# mcu.net
KiCad netlist of a schematic drawn in Altium Designer
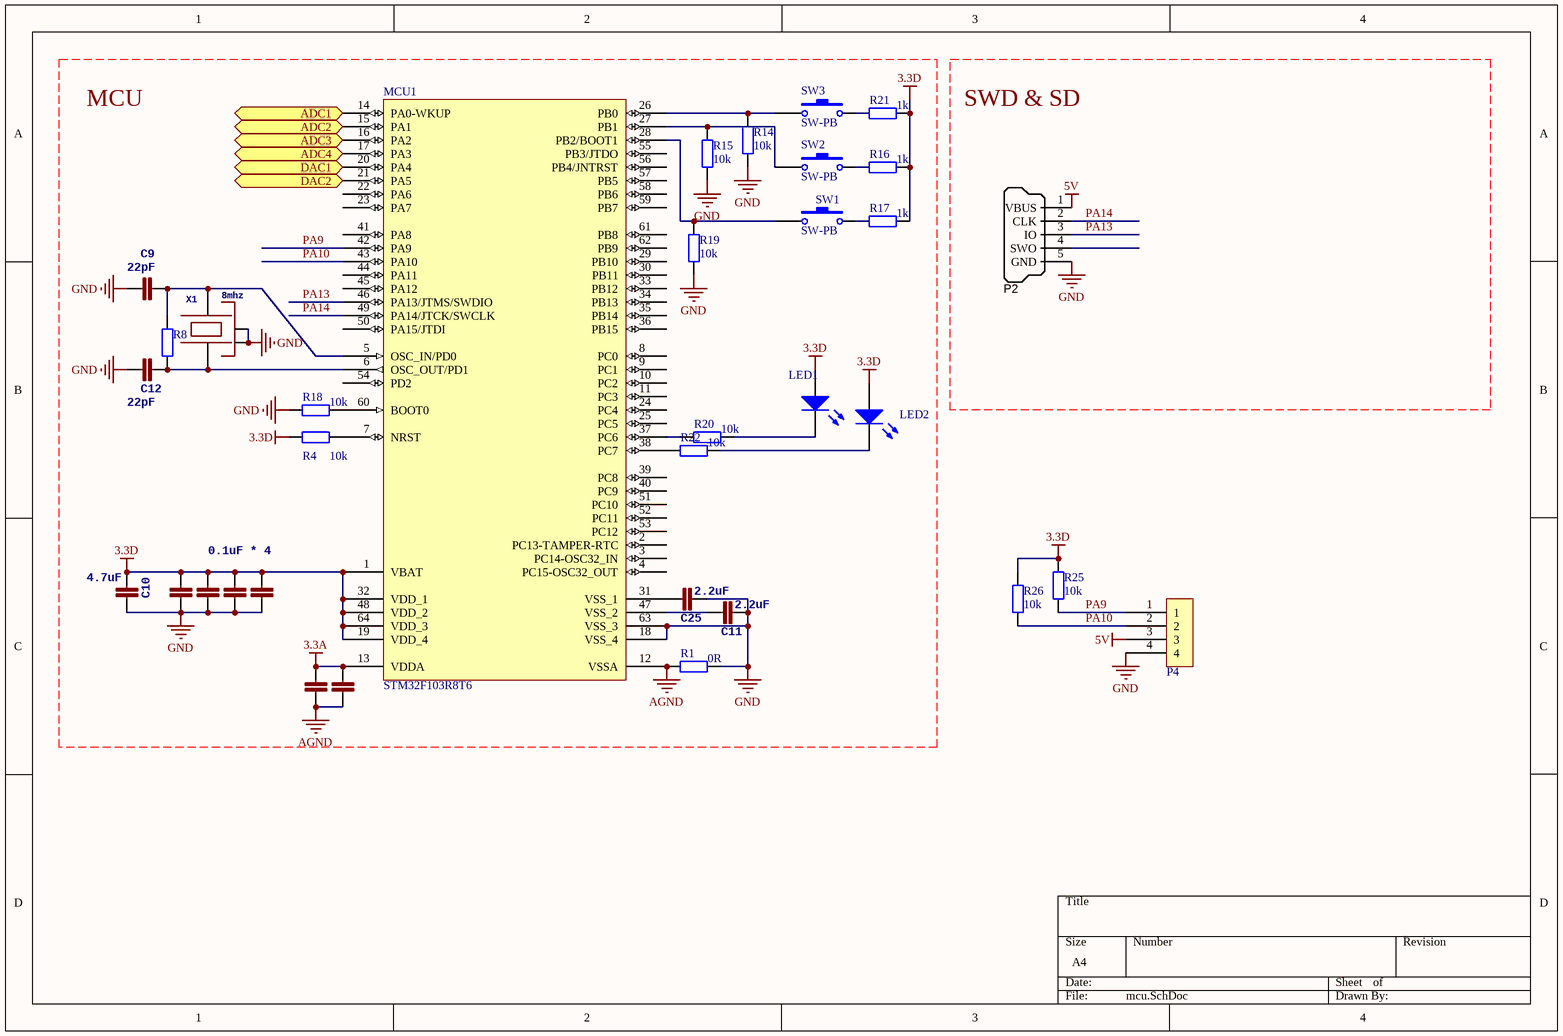
[diagram p0: mcu.SchDoc]

(export (version "E")
  (design (tool "Eeschema 10.0.6"))
  (components
    (comp (ref "C3")
      (value "1n")
      (footprint "0402")
      (description "<b>Capacitor</b>\nStandard 0603 ceramic capacitor, and 0.1\" leaded capacitor.")
      (fields (field (name "PARTNO") "CC0402ZRY5V7BB104"))
      (libsource (lib "") (part "CAP0402-CAP_3"))
    )
    (comp (ref "C4")
      (value "0.1uF * 4")
      (footprint "0402")
      (description "<b>Capacitor</b>\nStandard 0603 ceramic capacitor, and 0.1\" leaded capacitor.")
      (fields (field (name "PARTNO") "CC0402ZRY5V7BB104"))
      (libsource (lib "*") (part "CAP0402-CAP"))
    )
    (comp (ref "C5")
      (value "1n")
      (footprint "0402")
      (description "<b>Capacitor</b>\nStandard 0603 ceramic capacitor, and 0.1\" leaded capacitor.")
      (fields (field (name "PARTNO") "CC0402ZRY5V7BB104"))
      (libsource (lib "") (part "CAP0402-CAP_1"))
    )
    (comp (ref "C6")
      (value "1n")
      (footprint "0402")
      (description "<b>Capacitor</b>\nStandard 0603 ceramic capacitor, and 0.1\" leaded capacitor.")
      (fields (field (name "PARTNO") "CC0402ZRY5V7BB104"))
      (libsource (lib "") (part "CAP0402-CAP_1"))
    )
    (comp (ref "C7")
      (value "1n")
      (footprint "0402")
      (description "<b>Capacitor</b>\nStandard 0603 ceramic capacitor, and 0.1\" leaded capacitor.")
      (fields (field (name "PARTNO") "CC0402ZRY5V7BB104"))
      (libsource (lib "") (part "CAP0402-CAP_1"))
    )
    (comp (ref "C8")
      (value "1n")
      (footprint "0402")
      (description "<b>Capacitor</b>\nStandard 0603 ceramic capacitor, and 0.1\" leaded capacitor.")
      (fields (field (name "PARTNO") "CC0402ZRY5V7BB104"))
      (libsource (lib "") (part "CAP0402-CAP_3"))
    )
    (comp (ref "C9")
      (value "22pF")
      (footprint "0402")
      (description "<b>Capacitor</b>\nStandard 0603 ceramic capacitor, and 0.1\" leaded capacitor.")
      (fields (field (name "PARTNO") "CC0402ZRY5V7BB104"))
      (libsource (lib "pixhawk2") (part "CAP0402-CAP"))
    )
    (comp (ref "C10")
      (value "4.7uF")
      (footprint "0603")
      (description "<b>Capacitor</b>\nStandard 0603 ceramic capacitor, and 0.1\" leaded capacitor.")
      (fields (field (name "PARTNO") "CC0402ZRY5V7BB104"))
      (libsource (lib "") (part "CAP0402-CAP_1"))
    )
    (comp (ref "C11")
      (value "2.2uF")
      (footprint "0603")
      (description "<b>Capacitor</b>\nStandard 0603 ceramic capacitor, and 0.1\" leaded capacitor.")
      (fields (field (name "PARTNO") "CC0402ZRY5V7BB104"))
      (libsource (lib "") (part "CAP0402-CAP_2"))
    )
    (comp (ref "C12")
      (value "22pF")
      (footprint "0402")
      (description "<b>Capacitor</b>\nStandard 0603 ceramic capacitor, and 0.1\" leaded capacitor.")
      (fields (field (name "PARTNO") "CC0402ZRY5V7BB104"))
      (libsource (lib "") (part "CAP0402-CAP_1"))
    )
    (comp (ref "C25")
      (value "2.2uF")
      (footprint "0603")
      (description "<b>Capacitor</b>\nStandard 0603 ceramic capacitor, and 0.1\" leaded capacitor.")
      (fields (field (name "PARTNO") "CC0402ZRY5V7BB104"))
      (libsource (lib "") (part "CAP0402-CAP_2"))
    )
    (comp (ref "LED1")
      (value "LED0")
      (footprint "0603")
      (description "Typical INFRARED GaAs LED")
      (fields (field (name "PUBLISHER") "Altium Limited"))
      (libsource (lib "Miscellaneous Devices") (part "LED0"))
    )
    (comp (ref "LED2")
      (value "LED0")
      (footprint "0603")
      (description "Typical INFRARED GaAs LED")
      (fields (field (name "PUBLISHER") "Altium Limited"))
      (libsource (lib "Miscellaneous Devices") (part "LED0"))
    )
    (comp (ref "MCU1")
      (value "STM32F103R8T6")
      (footprint "LQFP64_N")
      (description "STM32 ARM-based 32-bit MCU with 64 Kbytes Flash, 64-pin LQFP, Industrial Temperature")
      (fields (field (name "PUBLISHER") "*"))
      (libsource (lib "ST Microcontroller 32-Bit STM32 SCH") (part "STM32F103R8T6"))
    )
    (comp (ref "P2")
      (value "SWD_MicroUSB")
      (footprint "MICRO-YZX")
      (description "Connector SMD USB Micro Type B middle mount")
      (libsource (lib "sch") (part "SWD_MicroUSB"))
    )
    (comp (ref "P4") (value "UART/I2C") (footprint "4pSocket") (libsource (lib "sch") (part "4PSocket")))
    (comp (ref "R1")
      (value "0R")
      (footprint "0402")
      (description "Resistor")
      (fields (field (name "PUBLISHER") "Altium Limited"))
      (libsource (lib "") (part "Res2_1"))
    )
    (comp (ref "R4")
      (value "10k")
      (footprint "0402")
      (description "Resistor")
      (fields (field (name "PUBLISHER") "Altium Limited"))
      (libsource (lib "") (part "Res2_2"))
    )
    (comp (ref "R8")
      (value "~")
      (footprint "0402")
      (description "Resistor")
      (fields (field (name "PUBLISHER") "Altium Limited"))
      (libsource (lib "Miscellaneous Devices") (part "Res2"))
    )
    (comp (ref "R14")
      (value "10k")
      (footprint "0402")
      (description "Resistor")
      (fields (field (name "PUBLISHER") "Altium Limited"))
      (libsource (lib "Miscellaneous Devices") (part "Res2"))
    )
    (comp (ref "R15")
      (value "10k")
      (footprint "0402")
      (description "Resistor")
      (fields (field (name "PUBLISHER") "Altium Limited"))
      (libsource (lib "Miscellaneous Devices") (part "Res2"))
    )
    (comp (ref "R16")
      (value "1k")
      (footprint "0402")
      (description "Resistor")
      (fields (field (name "PUBLISHER") "Altium Limited"))
      (libsource (lib "") (part "Res2_1"))
    )
    (comp (ref "R17")
      (value "1k")
      (footprint "0402")
      (description "Resistor")
      (fields (field (name "PUBLISHER") "Altium Limited"))
      (libsource (lib "") (part "Res2_1"))
    )
    (comp (ref "R18")
      (value "10k")
      (footprint "0402")
      (description "Resistor")
      (fields (field (name "PUBLISHER") "Altium Limited"))
      (libsource (lib "") (part "Res2_1"))
    )
    (comp (ref "R19")
      (value "10k")
      (footprint "0402")
      (description "Resistor")
      (fields (field (name "PUBLISHER") "Altium Limited"))
      (libsource (lib "Miscellaneous Devices") (part "Res2"))
    )
    (comp (ref "R20")
      (value "10k")
      (footprint "0402")
      (description "Resistor")
      (fields (field (name "PUBLISHER") "Altium Limited"))
      (libsource (lib "") (part "Res2_1"))
    )
    (comp (ref "R21")
      (value "1k")
      (footprint "0402")
      (description "Resistor")
      (fields (field (name "PUBLISHER") "Altium Limited"))
      (libsource (lib "") (part "Res2_1"))
    )
    (comp (ref "R22")
      (value "10k")
      (footprint "0402")
      (description "Resistor")
      (fields (field (name "PUBLISHER") "Altium Limited"))
      (libsource (lib "") (part "Res2_1"))
    )
    (comp (ref "R25")
      (value "10k")
      (footprint "0402")
      (description "Resistor")
      (fields (field (name "PUBLISHER") "Altium Limited"))
      (libsource (lib "Miscellaneous Devices") (part "Res2"))
    )
    (comp (ref "R26")
      (value "10k")
      (footprint "0402")
      (description "Resistor")
      (fields (field (name "PUBLISHER") "Altium Limited"))
      (libsource (lib "Miscellaneous Devices") (part "Res2"))
    )
    (comp (ref "SW1")
      (value "SW-PB")
      (footprint "SW3x4")
      (description "Switch")
      (fields (field (name "PUBLISHER") "Altium Limited"))
      (libsource (lib "Miscellaneous Devices") (part "SW-PB"))
    )
    (comp (ref "SW2")
      (value "SW-PB")
      (footprint "SW3x4")
      (description "Switch")
      (fields (field (name "PUBLISHER") "Altium Limited"))
      (libsource (lib "Miscellaneous Devices") (part "SW-PB"))
    )
    (comp (ref "SW3")
      (value "SW-PB")
      (footprint "SW3x4")
      (description "Switch")
      (fields (field (name "PUBLISHER") "Altium Limited"))
      (libsource (lib "Miscellaneous Devices") (part "SW-PB"))
    )
    (comp (ref "X1")
      (value "8mhz")
      (footprint "OSCILLATOR-3.2X2.5")
      (description "Crystal Oscillator in 3.2x2.5 SMD")
      (libsource (lib "sch") (part "OSCILLATOR-3.2X2.5"))
    )
  )
  (nets
    (net (code "1") (name "/ADC1") (class "Default")
      (node (ref "MCU1") (pin "14") (pinfunction "PA0-WKUP_14") (pintype "bidirectional"))
    )
    (net (code "2") (name "/ADC2") (class "Default")
      (node (ref "MCU1") (pin "15") (pinfunction "PA1_15") (pintype "bidirectional"))
    )
    (net (code "3") (name "/ADC3") (class "Default")
      (node (ref "MCU1") (pin "16") (pinfunction "PA2_16") (pintype "bidirectional"))
    )
    (net (code "4") (name "/ADC4") (class "Default")
      (node (ref "MCU1") (pin "17") (pinfunction "PA3_17") (pintype "bidirectional"))
    )
    (net (code "5") (name "/DAC1") (class "Default")
      (node (ref "MCU1") (pin "20") (pinfunction "PA4_20") (pintype "bidirectional"))
    )
    (net (code "6") (name "/DAC2") (class "Default")
      (node (ref "MCU1") (pin "21") (pinfunction "PA5_21") (pintype "bidirectional"))
    )
    (net (code "7") (name "/PA9") (class "Default")
      (node (ref "MCU1") (pin "42") (pinfunction "PA9_42") (pintype "bidirectional"))
      (node (ref "P4") (pin "1") (pinfunction "1_1") (pintype "passive"))
      (node (ref "R25") (pin "1") (pinfunction "1_1") (pintype "passive"))
    )
    (net (code "8") (name "/PA10") (class "Default")
      (node (ref "MCU1") (pin "43") (pinfunction "PA10_43") (pintype "bidirectional"))
      (node (ref "P4") (pin "2") (pinfunction "2_2") (pintype "passive"))
      (node (ref "R26") (pin "1") (pinfunction "1_1") (pintype "passive"))
    )
    (net (code "9") (name "/PA13") (class "Default")
      (node (ref "MCU1") (pin "46") (pinfunction "PA13/JTMS/SWDIO_46") (pintype "bidirectional"))
      (node (ref "P2") (pin "3") (pinfunction "IO_3") (pintype "passive"))
    )
    (net (code "10") (name "/PA14") (class "Default")
      (node (ref "MCU1") (pin "49") (pinfunction "PA14/JTCK/SWCLK_49") (pintype "bidirectional"))
      (node (ref "P2") (pin "2") (pinfunction "CLK_2") (pintype "passive"))
    )
    (net (code "11") (name "3.3A") (class "Default")
      (node (ref "C3") (pin "1") (pinfunction "1_1") (pintype "passive"))
      (node (ref "C8") (pin "1") (pinfunction "1_1") (pintype "passive"))
      (node (ref "MCU1") (pin "13") (pinfunction "VDDA_13") (pintype "power_in"))
    )
    (net (code "12") (name "3.3D") (class "Default")
      (node (ref "C10") (pin "2") (pinfunction "2_2") (pintype "passive"))
      (node (ref "C4") (pin "2") (pinfunction "2_2") (pintype "passive"))
      (node (ref "C5") (pin "2") (pinfunction "2_2") (pintype "passive"))
      (node (ref "C6") (pin "2") (pinfunction "2_2") (pintype "passive"))
      (node (ref "C7") (pin "2") (pinfunction "2_2") (pintype "passive"))
      (node (ref "LED1") (pin "1") (pinfunction "A_1") (pintype "passive"))
      (node (ref "LED2") (pin "1") (pinfunction "A_1") (pintype "passive"))
      (node (ref "MCU1") (pin "1") (pinfunction "VBAT_1") (pintype "power_in"))
      (node (ref "MCU1") (pin "19") (pinfunction "VDD_4_19") (pintype "power_in"))
      (node (ref "MCU1") (pin "32") (pinfunction "VDD_1_32") (pintype "power_in"))
      (node (ref "MCU1") (pin "48") (pinfunction "VDD_2_48") (pintype "power_in"))
      (node (ref "MCU1") (pin "64") (pinfunction "VDD_3_64") (pintype "power_in"))
      (node (ref "R16") (pin "2") (pinfunction "2_2") (pintype "passive"))
      (node (ref "R17") (pin "2") (pinfunction "2_2") (pintype "passive"))
      (node (ref "R21") (pin "2") (pinfunction "2_2") (pintype "passive"))
      (node (ref "R25") (pin "2") (pinfunction "2_2") (pintype "passive"))
      (node (ref "R26") (pin "2") (pinfunction "2_2") (pintype "passive"))
      (node (ref "R4") (pin "2") (pinfunction "2_2") (pintype "passive"))
    )
    (net (code "13") (name "5V") (class "Default")
      (node (ref "P2") (pin "1") (pinfunction "VBUS_1") (pintype "passive"))
      (node (ref "P4") (pin "3") (pinfunction "3_3") (pintype "passive"))
    )
    (net (code "14") (name "AGND") (class "Default")
      (node (ref "C3") (pin "2") (pinfunction "2_2") (pintype "passive"))
      (node (ref "C8") (pin "2") (pinfunction "2_2") (pintype "passive"))
      (node (ref "MCU1") (pin "12") (pinfunction "VSSA_12") (pintype "power_in"))
      (node (ref "R1") (pin "1") (pinfunction "1_1") (pintype "passive"))
    )
    (net (code "15") (name "GND") (class "Default")
      (node (ref "C10") (pin "1") (pinfunction "1_1") (pintype "passive"))
      (node (ref "C11") (pin "2") (pinfunction "2_2") (pintype "passive"))
      (node (ref "C12") (pin "2") (pinfunction "2_2") (pintype "passive"))
      (node (ref "C25") (pin "2") (pinfunction "2_2") (pintype "passive"))
      (node (ref "C4") (pin "1") (pinfunction "1_1") (pintype "passive"))
      (node (ref "C5") (pin "1") (pinfunction "1_1") (pintype "passive"))
      (node (ref "C6") (pin "1") (pinfunction "1_1") (pintype "passive"))
      (node (ref "C7") (pin "1") (pinfunction "1_1") (pintype "passive"))
      (node (ref "C9") (pin "2") (pinfunction "2_2") (pintype "passive"))
      (node (ref "MCU1") (pin "18") (pinfunction "VSS_4_18") (pintype "power_in"))
      (node (ref "MCU1") (pin "63") (pinfunction "VSS_3_63") (pintype "power_in"))
      (node (ref "P2") (pin "5") (pinfunction "GND_5") (pintype "passive"))
      (node (ref "P4") (pin "4") (pinfunction "4_4") (pintype "passive"))
      (node (ref "R1") (pin "2") (pinfunction "2_2") (pintype "passive"))
      (node (ref "R14") (pin "1") (pinfunction "1_1") (pintype "passive"))
      (node (ref "R15") (pin "1") (pinfunction "1_1") (pintype "passive"))
      (node (ref "R18") (pin "1") (pinfunction "1_1") (pintype "passive"))
      (node (ref "R19") (pin "1") (pinfunction "1_1") (pintype "passive"))
      (node (ref "X1") (pin "2") (pinfunction "NC_2_2") (pintype "open_emitter"))
      (node (ref "X1") (pin "4") (pinfunction "NC_4_4") (pintype "open_emitter"))
    )
    (net (code "16") (name "Net-(LED1-K)") (class "Default")
      (node (ref "LED1") (pin "2") (pinfunction "K_2") (pintype "passive"))
      (node (ref "R20") (pin "2") (pinfunction "2_2") (pintype "passive"))
    )
    (net (code "17") (name "Net-(LED2-K)") (class "Default")
      (node (ref "LED2") (pin "2") (pinfunction "K_2") (pintype "passive"))
      (node (ref "R22") (pin "2") (pinfunction "2_2") (pintype "passive"))
    )
    (net (code "18") (name "Net-(MCU1-BOOT0)") (class "Default")
      (node (ref "MCU1") (pin "60") (pinfunction "BOOT0_60") (pintype "input"))
      (node (ref "R18") (pin "2") (pinfunction "2_2") (pintype "passive"))
    )
    (net (code "19") (name "Net-(MCU1-NRST)") (class "Default")
      (node (ref "MCU1") (pin "7") (pinfunction "NRST_7") (pintype "bidirectional"))
      (node (ref "R4") (pin "1") (pinfunction "1_1") (pintype "passive"))
    )
    (net (code "20") (name "Net-(MCU1-OSC_IN{slash}PD0)") (class "Default")
      (node (ref "C9") (pin "1") (pinfunction "1_1") (pintype "passive"))
      (node (ref "MCU1") (pin "5") (pinfunction "OSC_IN/PD0_5") (pintype "input"))
      (node (ref "R8") (pin "2") (pinfunction "2_2") (pintype "passive"))
      (node (ref "X1") (pin "3") (pinfunction "3_3") (pintype "passive"))
    )
    (net (code "21") (name "Net-(MCU1-OSC_OUT{slash}PD1)") (class "Default")
      (node (ref "C12") (pin "1") (pinfunction "1_1") (pintype "passive"))
      (node (ref "MCU1") (pin "6") (pinfunction "OSC_OUT/PD1_6") (pintype "output"))
      (node (ref "R8") (pin "1") (pinfunction "1_1") (pintype "passive"))
      (node (ref "X1") (pin "1") (pinfunction "1_1") (pintype "passive"))
    )
    (net (code "22") (name "Net-(MCU1-PB0)") (class "Default")
      (node (ref "MCU1") (pin "26") (pinfunction "PB0_26") (pintype "bidirectional"))
      (node (ref "R14") (pin "2") (pinfunction "2_2") (pintype "passive"))
      (node (ref "SW3") (pin "1") (pinfunction "1_1") (pintype "passive"))
    )
    (net (code "23") (name "Net-(MCU1-PB1)") (class "Default")
      (node (ref "MCU1") (pin "27") (pinfunction "PB1_27") (pintype "bidirectional"))
      (node (ref "R15") (pin "2") (pinfunction "2_2") (pintype "passive"))
      (node (ref "SW2") (pin "1") (pinfunction "1_1") (pintype "passive"))
    )
    (net (code "24") (name "Net-(MCU1-PB2{slash}BOOT1)") (class "Default")
      (node (ref "MCU1") (pin "28") (pinfunction "PB2/BOOT1_28") (pintype "bidirectional"))
      (node (ref "R19") (pin "2") (pinfunction "2_2") (pintype "passive"))
      (node (ref "SW1") (pin "1") (pinfunction "1_1") (pintype "passive"))
    )
    (net (code "25") (name "Net-(MCU1-PC6)") (class "Default")
      (node (ref "MCU1") (pin "37") (pinfunction "PC6_37") (pintype "bidirectional"))
      (node (ref "R20") (pin "1") (pinfunction "1_1") (pintype "passive"))
    )
    (net (code "26") (name "Net-(MCU1-PC7)") (class "Default")
      (node (ref "MCU1") (pin "38") (pinfunction "PC7_38") (pintype "bidirectional"))
      (node (ref "R22") (pin "1") (pinfunction "1_1") (pintype "passive"))
    )
    (net (code "27") (name "Net-(MCU1-VSS_1)") (class "Default")
      (node (ref "C25") (pin "1") (pinfunction "1_1") (pintype "passive"))
      (node (ref "MCU1") (pin "31") (pinfunction "VSS_1_31") (pintype "power_in"))
    )
    (net (code "28") (name "Net-(MCU1-VSS_2)") (class "Default")
      (node (ref "C11") (pin "1") (pinfunction "1_1") (pintype "passive"))
      (node (ref "MCU1") (pin "47") (pinfunction "VSS_2_47") (pintype "power_in"))
    )
    (net (code "29") (name "Net-(R16-Pad1)") (class "Default")
      (node (ref "R16") (pin "1") (pinfunction "1_1") (pintype "passive"))
      (node (ref "SW2") (pin "2") (pinfunction "2_2") (pintype "passive"))
    )
    (net (code "30") (name "Net-(R17-Pad1)") (class "Default")
      (node (ref "R17") (pin "1") (pinfunction "1_1") (pintype "passive"))
      (node (ref "SW1") (pin "2") (pinfunction "2_2") (pintype "passive"))
    )
    (net (code "31") (name "Net-(R21-Pad1)") (class "Default")
      (node (ref "R21") (pin "1") (pinfunction "1_1") (pintype "passive"))
      (node (ref "SW3") (pin "2") (pinfunction "2_2") (pintype "passive"))
    )
    (net (code "32") (name "unconnected-(MCU1-PA6-Pad22)") (class "Default")
      (node (ref "MCU1") (pin "22") (pinfunction "PA6_22") (pintype "bidirectional"))
    )
    (net (code "33") (name "unconnected-(MCU1-PA7-Pad23)") (class "Default")
      (node (ref "MCU1") (pin "23") (pinfunction "PA7_23") (pintype "bidirectional"))
    )
    (net (code "34") (name "unconnected-(MCU1-PA8-Pad41)") (class "Default")
      (node (ref "MCU1") (pin "41") (pinfunction "PA8_41") (pintype "bidirectional"))
    )
    (net (code "35") (name "unconnected-(MCU1-PA11-Pad44)") (class "Default")
      (node (ref "MCU1") (pin "44") (pinfunction "PA11_44") (pintype "bidirectional"))
    )
    (net (code "36") (name "unconnected-(MCU1-PA12-Pad45)") (class "Default")
      (node (ref "MCU1") (pin "45") (pinfunction "PA12_45") (pintype "bidirectional"))
    )
    (net (code "37") (name "unconnected-(MCU1-PA15{slash}JTDI-Pad50)") (class "Default")
      (node (ref "MCU1") (pin "50") (pinfunction "PA15/JTDI_50") (pintype "bidirectional"))
    )
    (net (code "38") (name "unconnected-(MCU1-PB3{slash}JTDO-Pad55)") (class "Default")
      (node (ref "MCU1") (pin "55") (pinfunction "PB3/JTDO_55") (pintype "bidirectional"))
    )
    (net (code "39") (name "unconnected-(MCU1-PB4{slash}JNTRST-Pad56)") (class "Default")
      (node (ref "MCU1") (pin "56") (pinfunction "PB4/JNTRST_56") (pintype "bidirectional"))
    )
    (net (code "40") (name "unconnected-(MCU1-PB5-Pad57)") (class "Default")
      (node (ref "MCU1") (pin "57") (pinfunction "PB5_57") (pintype "bidirectional"))
    )
    (net (code "41") (name "unconnected-(MCU1-PB6-Pad58)") (class "Default")
      (node (ref "MCU1") (pin "58") (pinfunction "PB6_58") (pintype "bidirectional"))
    )
    (net (code "42") (name "unconnected-(MCU1-PB7-Pad59)") (class "Default")
      (node (ref "MCU1") (pin "59") (pinfunction "PB7_59") (pintype "bidirectional"))
    )
    (net (code "43") (name "unconnected-(MCU1-PB8-Pad61)") (class "Default")
      (node (ref "MCU1") (pin "61") (pinfunction "PB8_61") (pintype "bidirectional"))
    )
    (net (code "44") (name "unconnected-(MCU1-PB9-Pad62)") (class "Default")
      (node (ref "MCU1") (pin "62") (pinfunction "PB9_62") (pintype "bidirectional"))
    )
    (net (code "45") (name "unconnected-(MCU1-PB10-Pad29)") (class "Default")
      (node (ref "MCU1") (pin "29") (pinfunction "PB10_29") (pintype "bidirectional"))
    )
    (net (code "46") (name "unconnected-(MCU1-PB11-Pad30)") (class "Default")
      (node (ref "MCU1") (pin "30") (pinfunction "PB11_30") (pintype "bidirectional"))
    )
    (net (code "47") (name "unconnected-(MCU1-PB12-Pad33)") (class "Default")
      (node (ref "MCU1") (pin "33") (pinfunction "PB12_33") (pintype "bidirectional"))
    )
    (net (code "48") (name "unconnected-(MCU1-PB13-Pad34)") (class "Default")
      (node (ref "MCU1") (pin "34") (pinfunction "PB13_34") (pintype "bidirectional"))
    )
    (net (code "49") (name "unconnected-(MCU1-PB14-Pad35)") (class "Default")
      (node (ref "MCU1") (pin "35") (pinfunction "PB14_35") (pintype "bidirectional"))
    )
    (net (code "50") (name "unconnected-(MCU1-PB15-Pad36)") (class "Default")
      (node (ref "MCU1") (pin "36") (pinfunction "PB15_36") (pintype "bidirectional"))
    )
    (net (code "51") (name "unconnected-(MCU1-PC0-Pad8)") (class "Default")
      (node (ref "MCU1") (pin "8") (pinfunction "PC0_8") (pintype "bidirectional"))
    )
    (net (code "52") (name "unconnected-(MCU1-PC1-Pad9)") (class "Default")
      (node (ref "MCU1") (pin "9") (pinfunction "PC1_9") (pintype "bidirectional"))
    )
    (net (code "53") (name "unconnected-(MCU1-PC2-Pad10)") (class "Default")
      (node (ref "MCU1") (pin "10") (pinfunction "PC2_10") (pintype "bidirectional"))
    )
    (net (code "54") (name "unconnected-(MCU1-PC3-Pad11)") (class "Default")
      (node (ref "MCU1") (pin "11") (pinfunction "PC3_11") (pintype "bidirectional"))
    )
    (net (code "55") (name "unconnected-(MCU1-PC4-Pad24)") (class "Default")
      (node (ref "MCU1") (pin "24") (pinfunction "PC4_24") (pintype "bidirectional"))
    )
    (net (code "56") (name "unconnected-(MCU1-PC5-Pad25)") (class "Default")
      (node (ref "MCU1") (pin "25") (pinfunction "PC5_25") (pintype "bidirectional"))
    )
    (net (code "57") (name "unconnected-(MCU1-PC8-Pad39)") (class "Default")
      (node (ref "MCU1") (pin "39") (pinfunction "PC8_39") (pintype "bidirectional"))
    )
    (net (code "58") (name "unconnected-(MCU1-PC9-Pad40)") (class "Default")
      (node (ref "MCU1") (pin "40") (pinfunction "PC9_40") (pintype "bidirectional"))
    )
    (net (code "59") (name "unconnected-(MCU1-PC10-Pad51)") (class "Default")
      (node (ref "MCU1") (pin "51") (pinfunction "PC10_51") (pintype "bidirectional"))
    )
    (net (code "60") (name "unconnected-(MCU1-PC11-Pad52)") (class "Default")
      (node (ref "MCU1") (pin "52") (pinfunction "PC11_52") (pintype "bidirectional"))
    )
    (net (code "61") (name "unconnected-(MCU1-PC12-Pad53)") (class "Default")
      (node (ref "MCU1") (pin "53") (pinfunction "PC12_53") (pintype "bidirectional"))
    )
    (net (code "62") (name "unconnected-(MCU1-PC13-TAMPER-RTC-Pad2)") (class "Default")
      (node (ref "MCU1") (pin "2") (pinfunction "PC13-TAMPER-RTC_2") (pintype "bidirectional"))
    )
    (net (code "63") (name "unconnected-(MCU1-PC14-OSC32_IN-Pad3)") (class "Default")
      (node (ref "MCU1") (pin "3") (pinfunction "PC14-OSC32_IN_3") (pintype "bidirectional"))
    )
    (net (code "64") (name "unconnected-(MCU1-PC15-OSC32_OUT-Pad4)") (class "Default")
      (node (ref "MCU1") (pin "4") (pinfunction "PC15-OSC32_OUT_4") (pintype "bidirectional"))
    )
    (net (code "65") (name "unconnected-(MCU1-PD2-Pad54)") (class "Default")
      (node (ref "MCU1") (pin "54") (pinfunction "PD2_54") (pintype "bidirectional"))
    )
    (net (code "66") (name "unconnected-(P2-SWO-Pad4)") (class "Default")
      (node (ref "P2") (pin "4") (pinfunction "SWO_4") (pintype "passive"))
    )
  )
)
